# A_PITCHROLL.net
KiCad netlist of a schematic drawn in Altium Designer
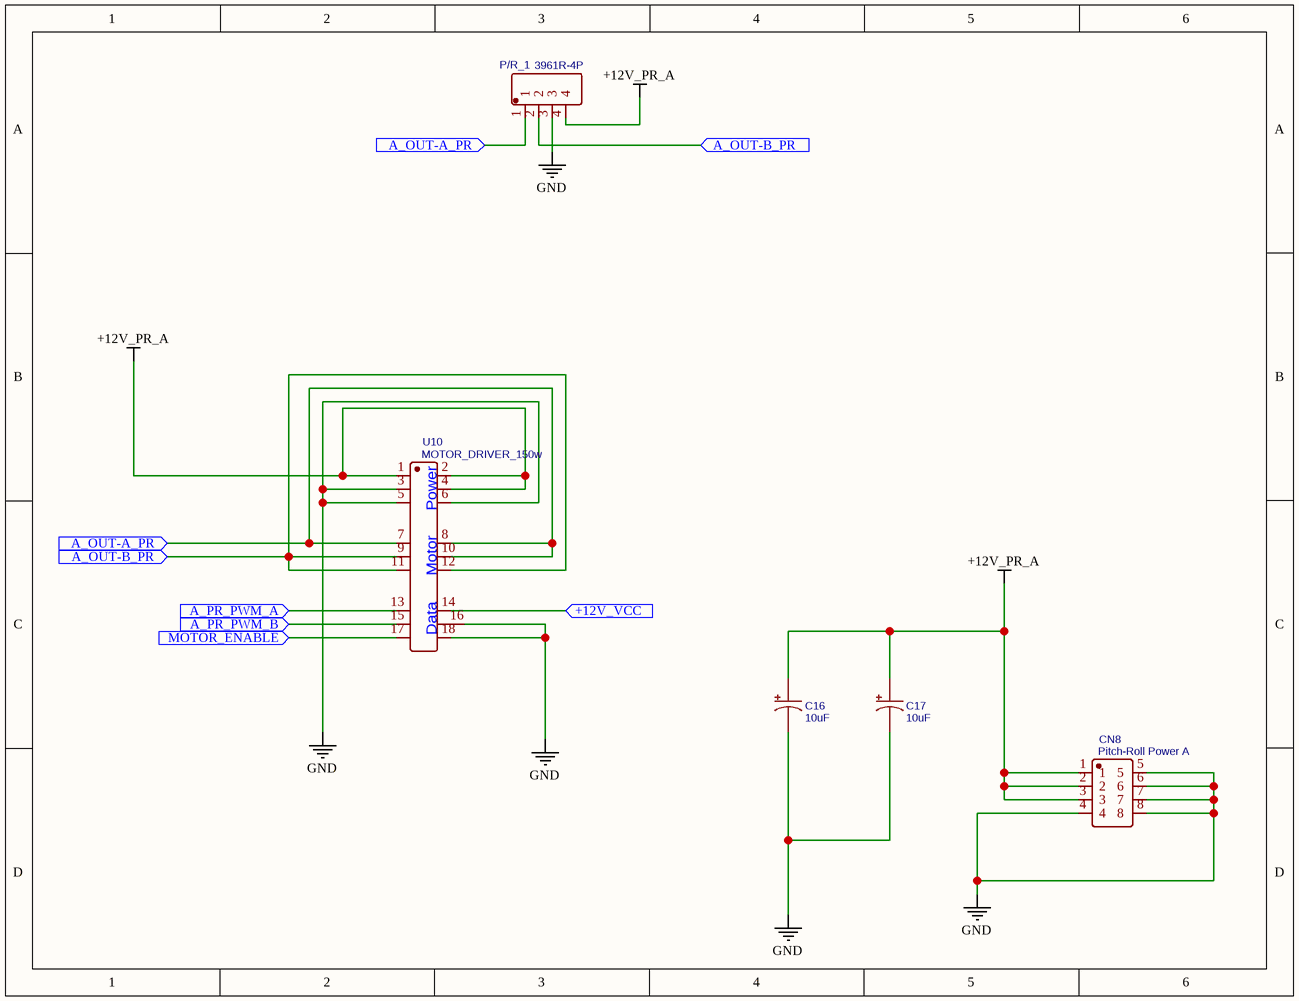
[diagram p0: A_PITCHROLL.schdoc]

(export (version "E")
  (design (tool "Eeschema 10.0.6"))
  (components
    (comp (ref "C16")
      (value "10uF")
      (fields
        (field (name "BOM_SUPPLIER PART") "C213486")
        (field (name "BOM_MANUFACTURER PART") "VT1E100M0405")
        (field (name "CONTRIBUTOR") "LCSC")
      )
      (libsource (lib "altium-import") (part "root_1_10uF_"))
    )
    (comp (ref "C17")
      (value "10uF")
      (fields
        (field (name "BOM_SUPPLIER PART") "C213486")
        (field (name "BOM_MANUFACTURER PART") "VT1E100M0405")
        (field (name "CONTRIBUTOR") "LCSC")
      )
      (libsource (lib "altium-import") (part "root_1_10uF_"))
    )
    (comp (ref "CN8")
      (value "Pitch-Roll Power A")
      (fields
        (field (name "BOM_SUPPLIER PART") "C519240")
        (field (name "BOM_MANUFACTURER PART") "X9357WV-2*04-N2SN")
        (field (name "CONTRIBUTOR") "LCSC")
      )
      (libsource (lib "altium-import") (part "root_0_Pitch-Roll Power A_"))
    )
    (comp (ref "P/R_1")
      (value "3961R-4P")
      (fields (field (name "BOM_SUPPLIER PART") "C138427") (field (name "CONTRIBUTOR") "LCSC"))
      (libsource (lib "altium-import") (part "root_1_3961R-4P_"))
    )
    (comp (ref "U10")
      (value "MOTOR_DRIVER_150w")
      (fields (field (name "CONTRIBUTOR") "digitalman"))
      (libsource (lib "altium-import") (part "root_3_MOTOR_DRIVER_150w_"))
    )
  )
  (nets
    (net (code "1") (name "+12V_PR_A") (class "Default")
      (node (ref "C16") (pin "1") (pinfunction "1_1") (pintype "passive"))
      (node (ref "C17") (pin "1") (pinfunction "1_1") (pintype "passive"))
      (node (ref "CN8") (pin "1") (pinfunction "1_1") (pintype "passive"))
      (node (ref "CN8") (pin "2") (pinfunction "2_2") (pintype "passive"))
      (node (ref "CN8") (pin "3") (pinfunction "3_3") (pintype "passive"))
      (node (ref "P/R_1") (pin "4") (pinfunction "4_4") (pintype "passive"))
      (node (ref "U10") (pin "1") (pinfunction "+12V_YAW_1") (pintype "passive"))
      (node (ref "U10") (pin "2") (pinfunction "+12V_YAW_2") (pintype "passive"))
      (node (ref "U10") (pin "4") (pinfunction "+12V_YAW_4") (pintype "passive"))
    )
    (net (code "2") (name "/+12V_VCC") (class "Default")
      (node (ref "U10") (pin "14") (pinfunction "+12V_VCC_14") (pintype "passive"))
    )
    (net (code "3") (name "/A_OUT-A_PR") (class "Default")
      (node (ref "P/R_1") (pin "1") (pinfunction "1_1") (pintype "passive"))
      (node (ref "U10") (pin "10") (pinfunction "OUT-A_YAW_10") (pintype "passive"))
      (node (ref "U10") (pin "7") (pinfunction "OUT-A_YAW_7") (pintype "passive"))
      (node (ref "U10") (pin "8") (pinfunction "OUT-A_YAW_8") (pintype "passive"))
    )
    (net (code "4") (name "/A_OUT-B_PR") (class "Default")
      (node (ref "P/R_1") (pin "2") (pinfunction "2_2") (pintype "passive"))
      (node (ref "U10") (pin "11") (pinfunction "OUT-B_YAW_11") (pintype "passive"))
      (node (ref "U10") (pin "12") (pinfunction "OUT-B_YAW_12") (pintype "passive"))
      (node (ref "U10") (pin "9") (pinfunction "OUT-B_YAW_9") (pintype "passive"))
    )
    (net (code "5") (name "/A_PR_PWM_A") (class "Default")
      (node (ref "U10") (pin "13") (pinfunction "PWM-A_YAW_13") (pintype "passive"))
    )
    (net (code "6") (name "/A_PR_PWM_B") (class "Default")
      (node (ref "U10") (pin "15") (pinfunction "PWM-B_YAW_15") (pintype "passive"))
    )
    (net (code "7") (name "/MOTOR_ENABLE") (class "Default")
      (node (ref "U10") (pin "17") (pinfunction "MOTOR_ENABLE_17") (pintype "passive"))
    )
    (net (code "8") (name "GND") (class "Default")
      (node (ref "C16") (pin "2") (pinfunction "2_2") (pintype "passive"))
      (node (ref "C17") (pin "2") (pinfunction "2_2") (pintype "passive"))
      (node (ref "CN8") (pin "4") (pinfunction "4_4") (pintype "passive"))
      (node (ref "CN8") (pin "5") (pinfunction "5_5") (pintype "passive"))
      (node (ref "CN8") (pin "6") (pinfunction "6_6") (pintype "passive"))
      (node (ref "CN8") (pin "7") (pinfunction "7_7") (pintype "passive"))
      (node (ref "CN8") (pin "8") (pinfunction "8_8") (pintype "passive"))
      (node (ref "P/R_1") (pin "3") (pinfunction "3_3") (pintype "passive"))
      (node (ref "U10") (pin "16") (pinfunction "GND_16") (pintype "passive"))
      (node (ref "U10") (pin "18") (pinfunction "GND_18") (pintype "passive"))
      (node (ref "U10") (pin "3") (pinfunction "GND_3") (pintype "passive"))
      (node (ref "U10") (pin "5") (pinfunction "GND_5") (pintype "passive"))
      (node (ref "U10") (pin "6") (pinfunction "GND_6") (pintype "passive"))
    )
  )
)
